# tiny-usb-aaaf5050.net
KiCad netlist of a schematic drawn in EAGLE
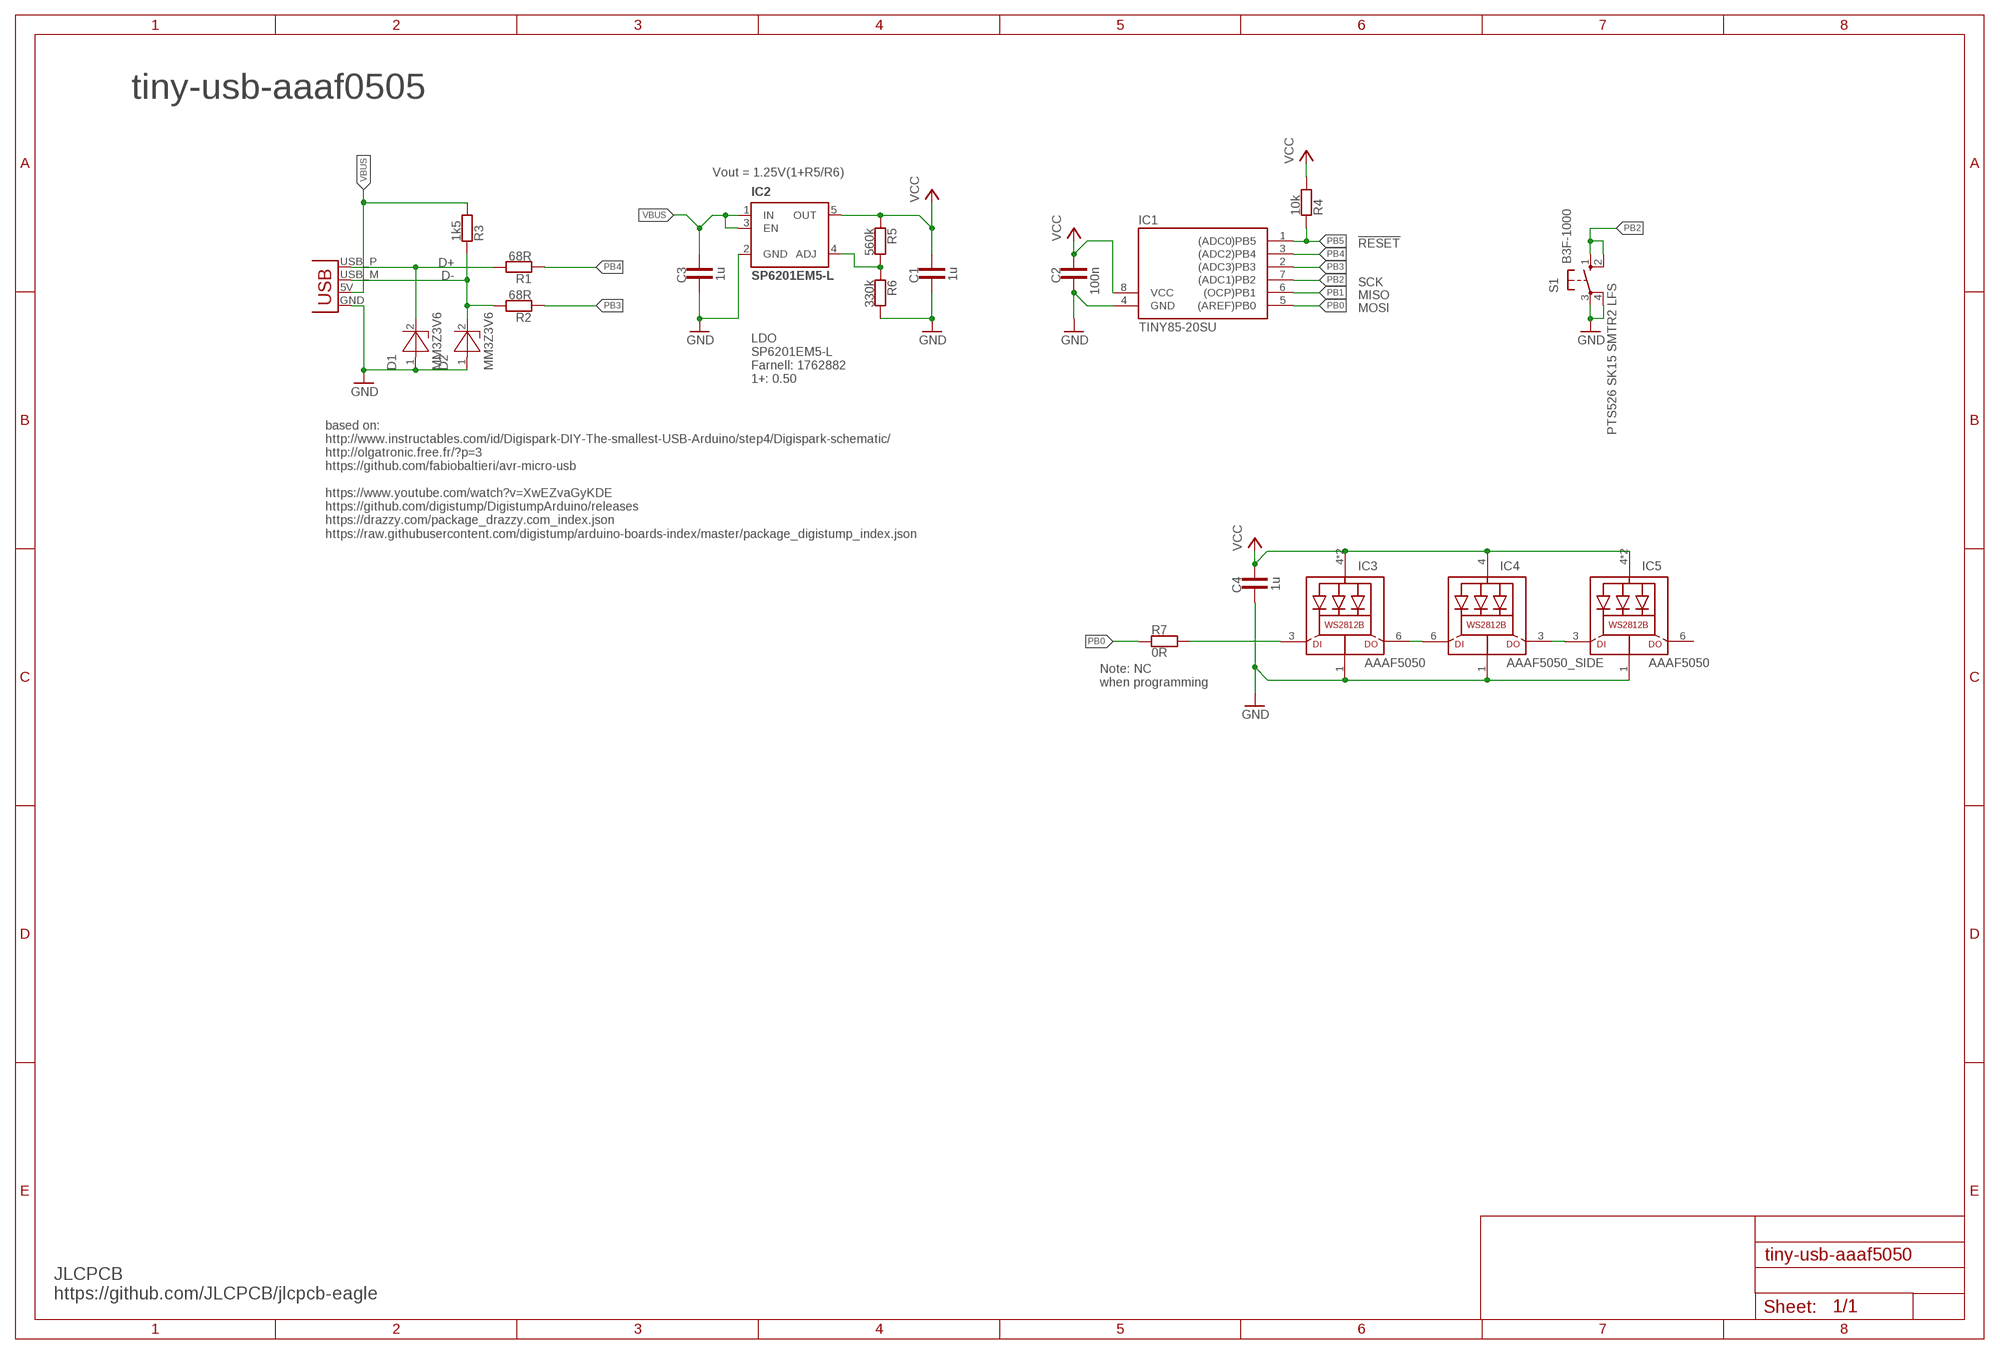
[diagram p0: schematic, sheet 1]

(export (version "E")
  (design (tool "Eeschema 10.0.6"))
  (components
    (comp (ref "C1")
      (value "1u")
      (footprint "eagle-import:0603MIL")
      (libsource (lib "eagle-import") (part "C0603"))
    )
    (comp (ref "C2")
      (value "100n")
      (footprint "eagle-import:0603MIL")
      (libsource (lib "eagle-import") (part "C0603"))
    )
    (comp (ref "C3")
      (value "1u")
      (footprint "eagle-import:0603MIL")
      (libsource (lib "eagle-import") (part "C0603"))
    )
    (comp (ref "C4")
      (value "1u")
      (footprint "eagle-import:0805MIL")
      (libsource (lib "eagle-import") (part "C0805"))
    )
    (comp (ref "D1")
      (value "MM3Z3V6")
      (footprint "eagle-import:SOD-923F")
      (libsource (lib "eagle-import") (part "MM3Z3V6"))
    )
    (comp (ref "D2")
      (value "MM3Z3V6")
      (footprint "eagle-import:SOD-923F")
      (libsource (lib "eagle-import") (part "MM3Z3V6"))
    )
    (comp (ref "IC1")
      (value "TINY85-20SU")
      (footprint "eagle-import:SOIC8")
      (libsource (lib "eagle-import") (part "TINY25-20SU"))
    )
    (comp (ref "IC2")
      (value "SP6201EM5-L")
      (footprint "eagle-import:SOT23-5")
      (libsource (lib "eagle-import") (part "SP6201EM5-L"))
    )
    (comp (ref "IC3")
      (value "AAAF5050")
      (footprint "eagle-import:AAAF5050")
      (libsource (lib "eagle-import") (part "AAAF5050"))
    )
    (comp (ref "IC4")
      (value "AAAF5050_SIDE")
      (footprint "eagle-import:AAAF5050_SIDE")
      (libsource (lib "eagle-import") (part "AAAF5050_SIDE"))
    )
    (comp (ref "IC5")
      (value "AAAF5050")
      (footprint "eagle-import:AAAF5050")
      (libsource (lib "eagle-import") (part "AAAF5050"))
    )
    (comp (ref "R1")
      (value "68R")
      (footprint "eagle-import:0603MIL")
      (libsource (lib "eagle-import") (part "R0603"))
    )
    (comp (ref "R2")
      (value "68R")
      (footprint "eagle-import:0603MIL")
      (libsource (lib "eagle-import") (part "R0603"))
    )
    (comp (ref "R3")
      (value "1k5")
      (footprint "eagle-import:0603MIL")
      (libsource (lib "eagle-import") (part "R0603"))
    )
    (comp (ref "R4")
      (value "10k")
      (footprint "eagle-import:0603MIL")
      (libsource (lib "eagle-import") (part "R0603"))
    )
    (comp (ref "R5")
      (value "560k")
      (footprint "eagle-import:0603MIL")
      (libsource (lib "eagle-import") (part "R0603"))
    )
    (comp (ref "R6")
      (value "330k")
      (footprint "eagle-import:0603MIL")
      (libsource (lib "eagle-import") (part "R0603"))
    )
    (comp (ref "R7")
      (value "0R")
      (footprint "eagle-import:0603MIL")
      (libsource (lib "eagle-import") (part "R0603"))
    )
    (comp (ref "S1")
      (value "B3F-1000")
      (footprint "eagle-import:B3F-10SMD")
      (libsource (lib "eagle-import") (part "10-XXSMD"))
    )
    (comp (ref "X1")
      (value "USBPCB")
      (footprint "eagle-import:USB-A-PCB")
      (libsource (lib "eagle-import") (part "USBPCB"))
    )
  )
  (nets
    (net (code "1") (name "/D+") (class "Default")
      (node (ref "D1") (pin "2") (pinfunction "K_2") (pintype "bidirectional"))
      (node (ref "R1") (pin "2") (pinfunction "2_2") (pintype "passive"))
      (node (ref "X1") (pin "USB_P") (pinfunction "D+_USB_P") (pintype "bidirectional"))
    )
    (net (code "2") (name "/D-") (class "Default")
      (node (ref "D2") (pin "2") (pinfunction "K_2") (pintype "bidirectional"))
      (node (ref "R2") (pin "2") (pinfunction "2_2") (pintype "passive"))
      (node (ref "R3") (pin "1") (pinfunction "1_1") (pintype "passive"))
      (node (ref "X1") (pin "USB_M") (pinfunction "D-_USB_M") (pintype "bidirectional"))
    )
    (net (code "3") (name "GND") (class "Default")
      (node (ref "C1") (pin "2") (pinfunction "2_2") (pintype "passive"))
      (node (ref "C2") (pin "2") (pinfunction "2_2") (pintype "passive"))
      (node (ref "C3") (pin "2") (pinfunction "2_2") (pintype "passive"))
      (node (ref "C4") (pin "2") (pinfunction "2_2") (pintype "passive"))
      (node (ref "D1") (pin "1") (pinfunction "A_1") (pintype "bidirectional"))
      (node (ref "D2") (pin "1") (pinfunction "A_1") (pintype "bidirectional"))
      (node (ref "IC1") (pin "4") (pinfunction "GND_4") (pintype "power_in"))
      (node (ref "IC2") (pin "2") (pinfunction "GND_2") (pintype "bidirectional"))
      (node (ref "IC3") (pin "1") (pinfunction "GND_1") (pintype "power_in"))
      (node (ref "IC4") (pin "1") (pinfunction "GND_1") (pintype "power_in"))
      (node (ref "IC5") (pin "1") (pinfunction "GND_1") (pintype "power_in"))
      (node (ref "R6") (pin "2") (pinfunction "2_2") (pintype "passive"))
      (node (ref "S1") (pin "3") (pinfunction "P_3") (pintype "passive"))
      (node (ref "S1") (pin "4") (pinfunction "P1_4") (pintype "passive"))
      (node (ref "X1") (pin "GND") (pinfunction "GND_GND") (pintype "bidirectional"))
    )
    (net (code "4") (name "Net-(IC2-ADJ)") (class "Default")
      (node (ref "IC2") (pin "4") (pinfunction "ADJ_4") (pintype "bidirectional"))
      (node (ref "R5") (pin "2") (pinfunction "2_2") (pintype "passive"))
      (node (ref "R6") (pin "1") (pinfunction "1_1") (pintype "passive"))
    )
    (net (code "5") (name "Net-(IC3-DI)") (class "Default")
      (node (ref "IC3") (pin "3") (pinfunction "DI_3") (pintype "input"))
      (node (ref "R7") (pin "2") (pinfunction "2_2") (pintype "passive"))
    )
    (net (code "6") (name "Net-(IC3-DO)") (class "Default")
      (node (ref "IC3") (pin "6") (pinfunction "DO_6") (pintype "output"))
      (node (ref "IC4") (pin "6") (pinfunction "DI_6") (pintype "input"))
    )
    (net (code "7") (name "Net-(IC4-DO)") (class "Default")
      (node (ref "IC4") (pin "3") (pinfunction "DO_3") (pintype "output"))
      (node (ref "IC5") (pin "3") (pinfunction "DI_3") (pintype "input"))
    )
    (net (code "8") (name "PB0") (class "Default")
      (node (ref "IC1") (pin "5") (pinfunction "(AREF)PB0_5") (pintype "bidirectional"))
      (node (ref "R7") (pin "1") (pinfunction "1_1") (pintype "passive"))
    )
    (net (code "9") (name "PB1") (class "Default")
      (node (ref "IC1") (pin "6") (pinfunction "(OCP)PB1_6") (pintype "bidirectional"))
    )
    (net (code "10") (name "PB2") (class "Default")
      (node (ref "IC1") (pin "7") (pinfunction "(ADC1)PB2_7") (pintype "bidirectional"))
      (node (ref "S1") (pin "1") (pinfunction "S_1") (pintype "passive"))
      (node (ref "S1") (pin "2") (pinfunction "S1_2") (pintype "passive"))
    )
    (net (code "11") (name "PB3") (class "Default")
      (node (ref "IC1") (pin "2") (pinfunction "(ADC3)PB3_2") (pintype "bidirectional"))
      (node (ref "R2") (pin "1") (pinfunction "1_1") (pintype "passive"))
    )
    (net (code "12") (name "PB4") (class "Default")
      (node (ref "IC1") (pin "3") (pinfunction "(ADC2)PB4_3") (pintype "bidirectional"))
      (node (ref "R1") (pin "1") (pinfunction "1_1") (pintype "passive"))
    )
    (net (code "13") (name "PB5") (class "Default")
      (node (ref "IC1") (pin "1") (pinfunction "(ADC0)PB5_1") (pintype "bidirectional"))
      (node (ref "R4") (pin "1") (pinfunction "1_1") (pintype "passive"))
    )
    (net (code "14") (name "VBUS") (class "Default")
      (node (ref "C3") (pin "1") (pinfunction "1_1") (pintype "passive"))
      (node (ref "IC2") (pin "1") (pinfunction "IN_1") (pintype "bidirectional"))
      (node (ref "IC2") (pin "3") (pinfunction "EN_3") (pintype "bidirectional"))
      (node (ref "R3") (pin "2") (pinfunction "2_2") (pintype "passive"))
      (node (ref "X1") (pin "5V") (pinfunction "VBUS_5V") (pintype "bidirectional"))
    )
    (net (code "15") (name "VCC") (class "Default")
      (node (ref "C1") (pin "1") (pinfunction "1_1") (pintype "passive"))
      (node (ref "C2") (pin "1") (pinfunction "1_1") (pintype "passive"))
      (node (ref "C4") (pin "1") (pinfunction "1_1") (pintype "passive"))
      (node (ref "IC1") (pin "8") (pinfunction "VCC_8") (pintype "power_in"))
      (node (ref "IC2") (pin "5") (pinfunction "OUT_5") (pintype "bidirectional"))
      (node (ref "IC3") (pin "4") (pinfunction "VDD_4") (pintype "power_in"))
      (node (ref "IC3") (pin "5") (pinfunction "VDD_5") (pintype "power_in"))
      (node (ref "IC4") (pin "4") (pinfunction "VDD_4") (pintype "power_in"))
      (node (ref "IC5") (pin "4") (pinfunction "VDD_4") (pintype "power_in"))
      (node (ref "IC5") (pin "5") (pinfunction "VDD_5") (pintype "power_in"))
      (node (ref "R4") (pin "2") (pinfunction "2_2") (pintype "passive"))
      (node (ref "R5") (pin "1") (pinfunction "1_1") (pintype "passive"))
    )
    (net (code "16") (name "unconnected-(IC5-DO-Pad6)") (class "Default")
      (node (ref "IC5") (pin "6") (pinfunction "DO_6") (pintype "output"))
    )
  )
)
